# matrixkeypad.net
KiCad netlist of a schematic drawn in Altium Designer
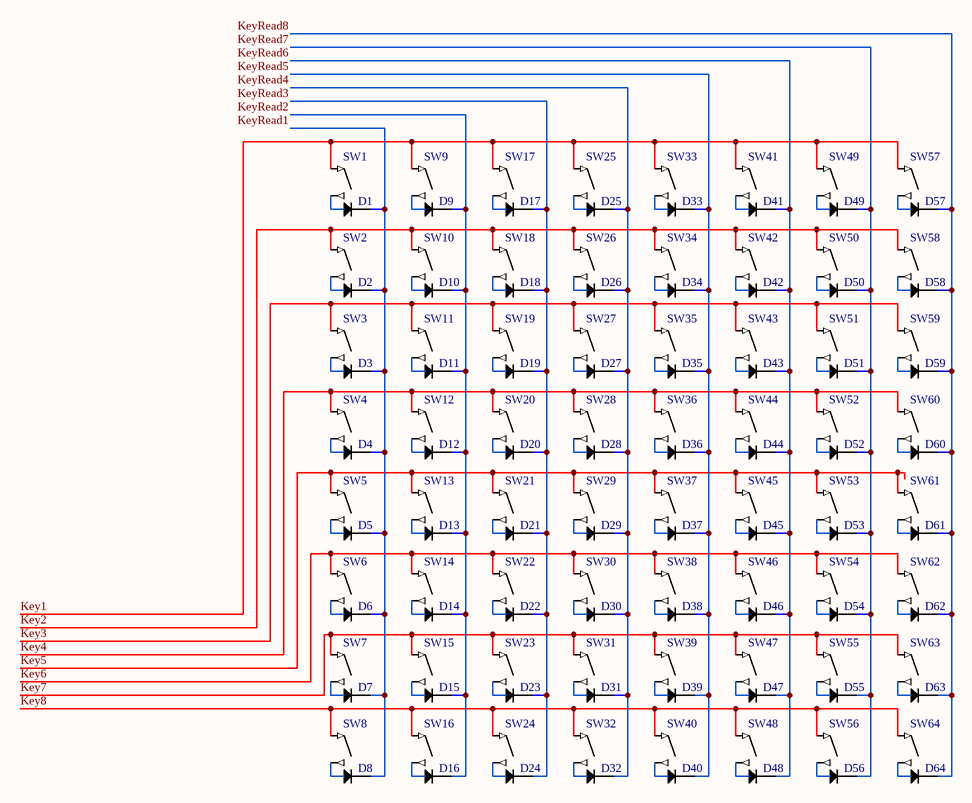
[diagram p0: matrixkeypad.SchDoc]

(export (version "E")
  (design (tool "Eeschema 10.0.6"))
  (components
    (comp (ref "D1") (value "1N4148") (footprint "SOD123") (libsource (lib "Project 64") (part "1N4148")))
    (comp (ref "D2") (value "1N4148") (footprint "SOD123") (libsource (lib "Project 64") (part "1N4148")))
    (comp (ref "D3") (value "1N4148") (footprint "SOD123") (libsource (lib "Project 64") (part "1N4148")))
    (comp (ref "D4") (value "1N4148") (footprint "SOD123") (libsource (lib "Project 64") (part "1N4148")))
    (comp (ref "D5") (value "1N4148") (footprint "SOD123") (libsource (lib "Project 64") (part "1N4148")))
    (comp (ref "D6") (value "1N4148") (footprint "SOD123") (libsource (lib "Project 64") (part "1N4148")))
    (comp (ref "D7") (value "1N4148") (footprint "SOD123") (libsource (lib "Project 64") (part "1N4148")))
    (comp (ref "D8") (value "1N4148") (footprint "SOD123") (libsource (lib "Project 64") (part "1N4148")))
    (comp (ref "D9") (value "1N4148") (footprint "SOD123") (libsource (lib "Project 64") (part "1N4148")))
    (comp (ref "D10") (value "1N4148") (footprint "SOD123") (libsource (lib "Project 64") (part "1N4148")))
    (comp (ref "D11") (value "1N4148") (footprint "SOD123") (libsource (lib "Project 64") (part "1N4148")))
    (comp (ref "D12") (value "1N4148") (footprint "SOD123") (libsource (lib "Project 64") (part "1N4148")))
    (comp (ref "D13") (value "1N4148") (footprint "SOD123") (libsource (lib "Project 64") (part "1N4148")))
    (comp (ref "D14") (value "1N4148") (footprint "SOD123") (libsource (lib "Project 64") (part "1N4148")))
    (comp (ref "D15") (value "1N4148") (footprint "SOD123") (libsource (lib "Project 64") (part "1N4148")))
    (comp (ref "D16") (value "1N4148") (footprint "SOD123") (libsource (lib "Project 64") (part "1N4148")))
    (comp (ref "D17") (value "1N4148") (footprint "SOD123") (libsource (lib "Project 64") (part "1N4148")))
    (comp (ref "D18") (value "1N4148") (footprint "SOD123") (libsource (lib "Project 64") (part "1N4148")))
    (comp (ref "D19") (value "1N4148") (footprint "SOD123") (libsource (lib "Project 64") (part "1N4148")))
    (comp (ref "D20") (value "1N4148") (footprint "SOD123") (libsource (lib "Project 64") (part "1N4148")))
    (comp (ref "D21") (value "1N4148") (footprint "SOD123") (libsource (lib "Project 64") (part "1N4148")))
    (comp (ref "D22") (value "1N4148") (footprint "SOD123") (libsource (lib "Project 64") (part "1N4148")))
    (comp (ref "D23") (value "1N4148") (footprint "SOD123") (libsource (lib "Project 64") (part "1N4148")))
    (comp (ref "D24") (value "1N4148") (footprint "SOD123") (libsource (lib "Project 64") (part "1N4148")))
    (comp (ref "D25") (value "1N4148") (footprint "SOD123") (libsource (lib "Project 64") (part "1N4148")))
    (comp (ref "D26") (value "1N4148") (footprint "SOD123") (libsource (lib "Project 64") (part "1N4148")))
    (comp (ref "D27") (value "1N4148") (footprint "SOD123") (libsource (lib "Project 64") (part "1N4148")))
    (comp (ref "D28") (value "1N4148") (footprint "SOD123") (libsource (lib "Project 64") (part "1N4148")))
    (comp (ref "D29") (value "1N4148") (footprint "SOD123") (libsource (lib "Project 64") (part "1N4148")))
    (comp (ref "D30") (value "1N4148") (footprint "SOD123") (libsource (lib "Project 64") (part "1N4148")))
    (comp (ref "D31") (value "1N4148") (footprint "SOD123") (libsource (lib "Project 64") (part "1N4148")))
    (comp (ref "D32") (value "1N4148") (footprint "SOD123") (libsource (lib "Project 64") (part "1N4148")))
    (comp (ref "D33") (value "1N4148") (footprint "SOD123") (libsource (lib "Project 64") (part "1N4148")))
    (comp (ref "D34") (value "1N4148") (footprint "SOD123") (libsource (lib "Project 64") (part "1N4148")))
    (comp (ref "D35") (value "1N4148") (footprint "SOD123") (libsource (lib "Project 64") (part "1N4148")))
    (comp (ref "D36") (value "1N4148") (footprint "SOD123") (libsource (lib "Project 64") (part "1N4148")))
    (comp (ref "D37") (value "1N4148") (footprint "SOD123") (libsource (lib "Project 64") (part "1N4148")))
    (comp (ref "D38") (value "1N4148") (footprint "SOD123") (libsource (lib "Project 64") (part "1N4148")))
    (comp (ref "D39") (value "1N4148") (footprint "SOD123") (libsource (lib "Project 64") (part "1N4148")))
    (comp (ref "D40") (value "1N4148") (footprint "SOD123") (libsource (lib "Project 64") (part "1N4148")))
    (comp (ref "D41") (value "1N4148") (footprint "SOD123") (libsource (lib "Project 64") (part "1N4148")))
    (comp (ref "D42") (value "1N4148") (footprint "SOD123") (libsource (lib "Project 64") (part "1N4148")))
    (comp (ref "D43") (value "1N4148") (footprint "SOD123") (libsource (lib "Project 64") (part "1N4148")))
    (comp (ref "D44") (value "1N4148") (footprint "SOD123") (libsource (lib "Project 64") (part "1N4148")))
    (comp (ref "D45") (value "1N4148") (footprint "SOD123") (libsource (lib "Project 64") (part "1N4148")))
    (comp (ref "D46") (value "1N4148") (footprint "SOD123") (libsource (lib "Project 64") (part "1N4148")))
    (comp (ref "D47") (value "1N4148") (footprint "SOD123") (libsource (lib "Project 64") (part "1N4148")))
    (comp (ref "D48") (value "1N4148") (footprint "SOD123") (libsource (lib "Project 64") (part "1N4148")))
    (comp (ref "D49") (value "1N4148") (footprint "SOD123") (libsource (lib "Project 64") (part "1N4148")))
    (comp (ref "D50") (value "1N4148") (footprint "SOD123") (libsource (lib "Project 64") (part "1N4148")))
    (comp (ref "D51") (value "1N4148") (footprint "SOD123") (libsource (lib "Project 64") (part "1N4148")))
    (comp (ref "D52") (value "1N4148") (footprint "SOD123") (libsource (lib "Project 64") (part "1N4148")))
    (comp (ref "D53") (value "1N4148") (footprint "SOD123") (libsource (lib "Project 64") (part "1N4148")))
    (comp (ref "D54") (value "1N4148") (footprint "SOD123") (libsource (lib "Project 64") (part "1N4148")))
    (comp (ref "D55") (value "1N4148") (footprint "SOD123") (libsource (lib "Project 64") (part "1N4148")))
    (comp (ref "D56") (value "1N4148") (footprint "SOD123") (libsource (lib "Project 64") (part "1N4148")))
    (comp (ref "D57") (value "1N4148") (footprint "SOD123") (libsource (lib "Project 64") (part "1N4148")))
    (comp (ref "D58") (value "1N4148") (footprint "SOD123") (libsource (lib "Project 64") (part "1N4148")))
    (comp (ref "D59") (value "1N4148") (footprint "SOD123") (libsource (lib "Project 64") (part "1N4148")))
    (comp (ref "D60") (value "1N4148") (footprint "SOD123") (libsource (lib "Project 64") (part "1N4148")))
    (comp (ref "D61") (value "1N4148") (footprint "SOD123") (libsource (lib "Project 64") (part "1N4148")))
    (comp (ref "D62") (value "1N4148") (footprint "SOD123") (libsource (lib "Project 64") (part "1N4148")))
    (comp (ref "D63") (value "1N4148") (footprint "SOD123") (libsource (lib "Project 64") (part "1N4148")))
    (comp (ref "D64") (value "1N4148") (footprint "SOD123") (libsource (lib "Project 64") (part "1N4148")))
    (comp (ref "SW1") (value "~") (footprint "PAD") (libsource (lib "Project 64") (part "SW")))
    (comp (ref "SW2") (value "~") (footprint "PAD") (libsource (lib "Project 64") (part "SW")))
    (comp (ref "SW3") (value "~") (footprint "PAD") (libsource (lib "Project 64") (part "SW")))
    (comp (ref "SW4") (value "~") (footprint "PAD") (libsource (lib "Project 64") (part "SW")))
    (comp (ref "SW5") (value "~") (footprint "PAD") (libsource (lib "Project 64") (part "SW")))
    (comp (ref "SW6") (value "~") (footprint "PAD") (libsource (lib "Project 64") (part "SW")))
    (comp (ref "SW7") (value "~") (footprint "PAD") (libsource (lib "Project 64") (part "SW")))
    (comp (ref "SW8") (value "~") (footprint "PAD") (libsource (lib "Project 64") (part "SW")))
    (comp (ref "SW9") (value "~") (footprint "PAD") (libsource (lib "Project 64") (part "SW")))
    (comp (ref "SW10") (value "~") (footprint "PAD") (libsource (lib "Project 64") (part "SW")))
    (comp (ref "SW11") (value "~") (footprint "PAD") (libsource (lib "Project 64") (part "SW")))
    (comp (ref "SW12") (value "~") (footprint "PAD") (libsource (lib "Project 64") (part "SW")))
    (comp (ref "SW13") (value "~") (footprint "PAD") (libsource (lib "Project 64") (part "SW")))
    (comp (ref "SW14") (value "~") (footprint "PAD") (libsource (lib "Project 64") (part "SW")))
    (comp (ref "SW15") (value "~") (footprint "PAD") (libsource (lib "Project 64") (part "SW")))
    (comp (ref "SW16") (value "~") (footprint "PAD") (libsource (lib "Project 64") (part "SW")))
    (comp (ref "SW17") (value "~") (footprint "PAD") (libsource (lib "Project 64") (part "SW")))
    (comp (ref "SW18") (value "~") (footprint "PAD") (libsource (lib "Project 64") (part "SW")))
    (comp (ref "SW19") (value "~") (footprint "PAD") (libsource (lib "Project 64") (part "SW")))
    (comp (ref "SW20") (value "~") (footprint "PAD") (libsource (lib "Project 64") (part "SW")))
    (comp (ref "SW21") (value "~") (footprint "PAD") (libsource (lib "Project 64") (part "SW")))
    (comp (ref "SW22") (value "~") (footprint "PAD") (libsource (lib "Project 64") (part "SW")))
    (comp (ref "SW23") (value "~") (footprint "PAD") (libsource (lib "Project 64") (part "SW")))
    (comp (ref "SW24") (value "~") (footprint "PAD") (libsource (lib "Project 64") (part "SW")))
    (comp (ref "SW25") (value "~") (footprint "PAD") (libsource (lib "Project 64") (part "SW")))
    (comp (ref "SW26") (value "~") (footprint "PAD") (libsource (lib "Project 64") (part "SW")))
    (comp (ref "SW27") (value "~") (footprint "PAD") (libsource (lib "Project 64") (part "SW")))
    (comp (ref "SW28") (value "~") (footprint "PAD") (libsource (lib "Project 64") (part "SW")))
    (comp (ref "SW29") (value "~") (footprint "PAD") (libsource (lib "Project 64") (part "SW")))
    (comp (ref "SW30") (value "~") (footprint "PAD") (libsource (lib "Project 64") (part "SW")))
    (comp (ref "SW31") (value "~") (footprint "PAD") (libsource (lib "Project 64") (part "SW")))
    (comp (ref "SW32") (value "~") (footprint "PAD") (libsource (lib "Project 64") (part "SW")))
    (comp (ref "SW33") (value "~") (footprint "PAD") (libsource (lib "Project 64") (part "SW")))
    (comp (ref "SW34") (value "~") (footprint "PAD") (libsource (lib "Project 64") (part "SW")))
    (comp (ref "SW35") (value "~") (footprint "PAD") (libsource (lib "Project 64") (part "SW")))
    (comp (ref "SW36") (value "~") (footprint "PAD") (libsource (lib "Project 64") (part "SW")))
    (comp (ref "SW37") (value "~") (footprint "PAD") (libsource (lib "Project 64") (part "SW")))
    (comp (ref "SW38") (value "~") (footprint "PAD") (libsource (lib "Project 64") (part "SW")))
    (comp (ref "SW39") (value "~") (footprint "PAD") (libsource (lib "Project 64") (part "SW")))
    (comp (ref "SW40") (value "~") (footprint "PAD") (libsource (lib "Project 64") (part "SW")))
    (comp (ref "SW41") (value "~") (footprint "PAD") (libsource (lib "Project 64") (part "SW")))
    (comp (ref "SW42") (value "~") (footprint "PAD") (libsource (lib "Project 64") (part "SW")))
    (comp (ref "SW43") (value "~") (footprint "PAD") (libsource (lib "Project 64") (part "SW")))
    (comp (ref "SW44") (value "~") (footprint "PAD") (libsource (lib "Project 64") (part "SW")))
    (comp (ref "SW45") (value "~") (footprint "PAD") (libsource (lib "Project 64") (part "SW")))
    (comp (ref "SW46") (value "~") (footprint "PAD") (libsource (lib "Project 64") (part "SW")))
    (comp (ref "SW47") (value "~") (footprint "PAD") (libsource (lib "Project 64") (part "SW")))
    (comp (ref "SW48") (value "~") (footprint "PAD") (libsource (lib "Project 64") (part "SW")))
    (comp (ref "SW49") (value "~") (footprint "PAD") (libsource (lib "Project 64") (part "SW")))
    (comp (ref "SW50") (value "~") (footprint "PAD") (libsource (lib "Project 64") (part "SW")))
    (comp (ref "SW51") (value "~") (footprint "PAD") (libsource (lib "Project 64") (part "SW")))
    (comp (ref "SW52") (value "~") (footprint "PAD") (libsource (lib "Project 64") (part "SW")))
    (comp (ref "SW53") (value "~") (footprint "PAD") (libsource (lib "Project 64") (part "SW")))
    (comp (ref "SW54") (value "~") (footprint "PAD") (libsource (lib "Project 64") (part "SW")))
    (comp (ref "SW55") (value "~") (footprint "PAD") (libsource (lib "Project 64") (part "SW")))
    (comp (ref "SW56") (value "~") (footprint "PAD") (libsource (lib "Project 64") (part "SW")))
    (comp (ref "SW57") (value "~") (footprint "PAD") (libsource (lib "Project 64") (part "SW")))
    (comp (ref "SW58") (value "~") (footprint "PAD") (libsource (lib "Project 64") (part "SW")))
    (comp (ref "SW59") (value "~") (footprint "PAD") (libsource (lib "Project 64") (part "SW")))
    (comp (ref "SW60") (value "~") (footprint "PAD") (libsource (lib "Project 64") (part "SW")))
    (comp (ref "SW61") (value "~") (footprint "PAD") (libsource (lib "Project 64") (part "SW")))
    (comp (ref "SW62") (value "~") (footprint "PAD") (libsource (lib "Project 64") (part "SW")))
    (comp (ref "SW63") (value "~") (footprint "PAD") (libsource (lib "Project 64") (part "SW")))
    (comp (ref "SW64") (value "~") (footprint "PAD") (libsource (lib "Project 64") (part "SW")))
  )
  (nets
    (net (code "1") (name "/Key1") (class "Default")
      (node (ref "SW1") (pin "1") (pinfunction "1_1") (pintype "input"))
      (node (ref "SW17") (pin "1") (pinfunction "1_1") (pintype "input"))
      (node (ref "SW25") (pin "1") (pinfunction "1_1") (pintype "input"))
      (node (ref "SW33") (pin "1") (pinfunction "1_1") (pintype "input"))
      (node (ref "SW41") (pin "1") (pinfunction "1_1") (pintype "input"))
      (node (ref "SW49") (pin "1") (pinfunction "1_1") (pintype "input"))
      (node (ref "SW57") (pin "1") (pinfunction "1_1") (pintype "input"))
      (node (ref "SW9") (pin "1") (pinfunction "1_1") (pintype "input"))
    )
    (net (code "2") (name "/Key2") (class "Default")
      (node (ref "SW10") (pin "1") (pinfunction "1_1") (pintype "input"))
      (node (ref "SW18") (pin "1") (pinfunction "1_1") (pintype "input"))
      (node (ref "SW2") (pin "1") (pinfunction "1_1") (pintype "input"))
      (node (ref "SW26") (pin "1") (pinfunction "1_1") (pintype "input"))
      (node (ref "SW34") (pin "1") (pinfunction "1_1") (pintype "input"))
      (node (ref "SW42") (pin "1") (pinfunction "1_1") (pintype "input"))
      (node (ref "SW50") (pin "1") (pinfunction "1_1") (pintype "input"))
      (node (ref "SW58") (pin "1") (pinfunction "1_1") (pintype "input"))
    )
    (net (code "3") (name "/Key3") (class "Default")
      (node (ref "SW11") (pin "1") (pinfunction "1_1") (pintype "input"))
      (node (ref "SW19") (pin "1") (pinfunction "1_1") (pintype "input"))
      (node (ref "SW27") (pin "1") (pinfunction "1_1") (pintype "input"))
      (node (ref "SW3") (pin "1") (pinfunction "1_1") (pintype "input"))
      (node (ref "SW35") (pin "1") (pinfunction "1_1") (pintype "input"))
      (node (ref "SW43") (pin "1") (pinfunction "1_1") (pintype "input"))
      (node (ref "SW51") (pin "1") (pinfunction "1_1") (pintype "input"))
      (node (ref "SW59") (pin "1") (pinfunction "1_1") (pintype "input"))
    )
    (net (code "4") (name "/Key4") (class "Default")
      (node (ref "SW12") (pin "1") (pinfunction "1_1") (pintype "input"))
      (node (ref "SW20") (pin "1") (pinfunction "1_1") (pintype "input"))
      (node (ref "SW28") (pin "1") (pinfunction "1_1") (pintype "input"))
      (node (ref "SW36") (pin "1") (pinfunction "1_1") (pintype "input"))
      (node (ref "SW4") (pin "1") (pinfunction "1_1") (pintype "input"))
      (node (ref "SW44") (pin "1") (pinfunction "1_1") (pintype "input"))
      (node (ref "SW52") (pin "1") (pinfunction "1_1") (pintype "input"))
      (node (ref "SW60") (pin "1") (pinfunction "1_1") (pintype "input"))
    )
    (net (code "5") (name "/Key5") (class "Default")
      (node (ref "SW13") (pin "1") (pinfunction "1_1") (pintype "input"))
      (node (ref "SW21") (pin "1") (pinfunction "1_1") (pintype "input"))
      (node (ref "SW29") (pin "1") (pinfunction "1_1") (pintype "input"))
      (node (ref "SW37") (pin "1") (pinfunction "1_1") (pintype "input"))
      (node (ref "SW45") (pin "1") (pinfunction "1_1") (pintype "input"))
      (node (ref "SW5") (pin "1") (pinfunction "1_1") (pintype "input"))
      (node (ref "SW53") (pin "1") (pinfunction "1_1") (pintype "input"))
      (node (ref "SW61") (pin "1") (pinfunction "1_1") (pintype "input"))
    )
    (net (code "6") (name "/Key6") (class "Default")
      (node (ref "SW14") (pin "1") (pinfunction "1_1") (pintype "input"))
      (node (ref "SW22") (pin "1") (pinfunction "1_1") (pintype "input"))
      (node (ref "SW30") (pin "1") (pinfunction "1_1") (pintype "input"))
      (node (ref "SW38") (pin "1") (pinfunction "1_1") (pintype "input"))
      (node (ref "SW46") (pin "1") (pinfunction "1_1") (pintype "input"))
      (node (ref "SW54") (pin "1") (pinfunction "1_1") (pintype "input"))
      (node (ref "SW6") (pin "1") (pinfunction "1_1") (pintype "input"))
      (node (ref "SW62") (pin "1") (pinfunction "1_1") (pintype "input"))
    )
    (net (code "7") (name "/Key7") (class "Default")
      (node (ref "SW15") (pin "1") (pinfunction "1_1") (pintype "input"))
      (node (ref "SW23") (pin "1") (pinfunction "1_1") (pintype "input"))
      (node (ref "SW31") (pin "1") (pinfunction "1_1") (pintype "input"))
      (node (ref "SW39") (pin "1") (pinfunction "1_1") (pintype "input"))
      (node (ref "SW47") (pin "1") (pinfunction "1_1") (pintype "input"))
      (node (ref "SW55") (pin "1") (pinfunction "1_1") (pintype "input"))
      (node (ref "SW63") (pin "1") (pinfunction "1_1") (pintype "input"))
      (node (ref "SW7") (pin "1") (pinfunction "1_1") (pintype "input"))
    )
    (net (code "8") (name "/Key8") (class "Default")
      (node (ref "SW16") (pin "1") (pinfunction "1_1") (pintype "input"))
      (node (ref "SW24") (pin "1") (pinfunction "1_1") (pintype "input"))
      (node (ref "SW32") (pin "1") (pinfunction "1_1") (pintype "input"))
      (node (ref "SW40") (pin "1") (pinfunction "1_1") (pintype "input"))
      (node (ref "SW48") (pin "1") (pinfunction "1_1") (pintype "input"))
      (node (ref "SW56") (pin "1") (pinfunction "1_1") (pintype "input"))
      (node (ref "SW64") (pin "1") (pinfunction "1_1") (pintype "input"))
      (node (ref "SW8") (pin "1") (pinfunction "1_1") (pintype "input"))
    )
    (net (code "9") (name "/KeyRead1") (class "Default")
      (node (ref "D1") (pin "2") (pinfunction "2_2") (pintype "passive"))
      (node (ref "D2") (pin "2") (pinfunction "2_2") (pintype "passive"))
      (node (ref "D3") (pin "2") (pinfunction "2_2") (pintype "passive"))
      (node (ref "D4") (pin "2") (pinfunction "2_2") (pintype "passive"))
      (node (ref "D5") (pin "2") (pinfunction "2_2") (pintype "passive"))
      (node (ref "D6") (pin "2") (pinfunction "2_2") (pintype "passive"))
      (node (ref "D7") (pin "2") (pinfunction "2_2") (pintype "passive"))
      (node (ref "D8") (pin "2") (pinfunction "2_2") (pintype "passive"))
    )
    (net (code "10") (name "/KeyRead2") (class "Default")
      (node (ref "D10") (pin "2") (pinfunction "2_2") (pintype "passive"))
      (node (ref "D11") (pin "2") (pinfunction "2_2") (pintype "passive"))
      (node (ref "D12") (pin "2") (pinfunction "2_2") (pintype "passive"))
      (node (ref "D13") (pin "2") (pinfunction "2_2") (pintype "passive"))
      (node (ref "D14") (pin "2") (pinfunction "2_2") (pintype "passive"))
      (node (ref "D15") (pin "2") (pinfunction "2_2") (pintype "passive"))
      (node (ref "D16") (pin "2") (pinfunction "2_2") (pintype "passive"))
      (node (ref "D9") (pin "2") (pinfunction "2_2") (pintype "passive"))
    )
    (net (code "11") (name "/KeyRead3") (class "Default")
      (node (ref "D17") (pin "2") (pinfunction "2_2") (pintype "passive"))
      (node (ref "D18") (pin "2") (pinfunction "2_2") (pintype "passive"))
      (node (ref "D19") (pin "2") (pinfunction "2_2") (pintype "passive"))
      (node (ref "D20") (pin "2") (pinfunction "2_2") (pintype "passive"))
      (node (ref "D21") (pin "2") (pinfunction "2_2") (pintype "passive"))
      (node (ref "D22") (pin "2") (pinfunction "2_2") (pintype "passive"))
      (node (ref "D23") (pin "2") (pinfunction "2_2") (pintype "passive"))
      (node (ref "D24") (pin "2") (pinfunction "2_2") (pintype "passive"))
    )
    (net (code "12") (name "/KeyRead4") (class "Default")
      (node (ref "D25") (pin "2") (pinfunction "2_2") (pintype "passive"))
      (node (ref "D26") (pin "2") (pinfunction "2_2") (pintype "passive"))
      (node (ref "D27") (pin "2") (pinfunction "2_2") (pintype "passive"))
      (node (ref "D28") (pin "2") (pinfunction "2_2") (pintype "passive"))
      (node (ref "D29") (pin "2") (pinfunction "2_2") (pintype "passive"))
      (node (ref "D30") (pin "2") (pinfunction "2_2") (pintype "passive"))
      (node (ref "D31") (pin "2") (pinfunction "2_2") (pintype "passive"))
      (node (ref "D32") (pin "2") (pinfunction "2_2") (pintype "passive"))
    )
    (net (code "13") (name "/KeyRead5") (class "Default")
      (node (ref "D33") (pin "2") (pinfunction "2_2") (pintype "passive"))
      (node (ref "D34") (pin "2") (pinfunction "2_2") (pintype "passive"))
      (node (ref "D35") (pin "2") (pinfunction "2_2") (pintype "passive"))
      (node (ref "D36") (pin "2") (pinfunction "2_2") (pintype "passive"))
      (node (ref "D37") (pin "2") (pinfunction "2_2") (pintype "passive"))
      (node (ref "D38") (pin "2") (pinfunction "2_2") (pintype "passive"))
      (node (ref "D39") (pin "2") (pinfunction "2_2") (pintype "passive"))
      (node (ref "D40") (pin "2") (pinfunction "2_2") (pintype "passive"))
    )
    (net (code "14") (name "/KeyRead6") (class "Default")
      (node (ref "D41") (pin "2") (pinfunction "2_2") (pintype "passive"))
      (node (ref "D42") (pin "2") (pinfunction "2_2") (pintype "passive"))
      (node (ref "D43") (pin "2") (pinfunction "2_2") (pintype "passive"))
      (node (ref "D44") (pin "2") (pinfunction "2_2") (pintype "passive"))
      (node (ref "D45") (pin "2") (pinfunction "2_2") (pintype "passive"))
      (node (ref "D46") (pin "2") (pinfunction "2_2") (pintype "passive"))
      (node (ref "D47") (pin "2") (pinfunction "2_2") (pintype "passive"))
      (node (ref "D48") (pin "2") (pinfunction "2_2") (pintype "passive"))
    )
    (net (code "15") (name "/KeyRead7") (class "Default")
      (node (ref "D49") (pin "2") (pinfunction "2_2") (pintype "passive"))
      (node (ref "D50") (pin "2") (pinfunction "2_2") (pintype "passive"))
      (node (ref "D51") (pin "2") (pinfunction "2_2") (pintype "passive"))
      (node (ref "D52") (pin "2") (pinfunction "2_2") (pintype "passive"))
      (node (ref "D53") (pin "2") (pinfunction "2_2") (pintype "passive"))
      (node (ref "D54") (pin "2") (pinfunction "2_2") (pintype "passive"))
      (node (ref "D55") (pin "2") (pinfunction "2_2") (pintype "passive"))
      (node (ref "D56") (pin "2") (pinfunction "2_2") (pintype "passive"))
    )
    (net (code "16") (name "/KeyRead8") (class "Default")
      (node (ref "D57") (pin "2") (pinfunction "2_2") (pintype "passive"))
      (node (ref "D58") (pin "2") (pinfunction "2_2") (pintype "passive"))
      (node (ref "D59") (pin "2") (pinfunction "2_2") (pintype "passive"))
      (node (ref "D60") (pin "2") (pinfunction "2_2") (pintype "passive"))
      (node (ref "D61") (pin "2") (pinfunction "2_2") (pintype "passive"))
      (node (ref "D62") (pin "2") (pinfunction "2_2") (pintype "passive"))
      (node (ref "D63") (pin "2") (pinfunction "2_2") (pintype "passive"))
      (node (ref "D64") (pin "2") (pinfunction "2_2") (pintype "passive"))
    )
    (net (code "17") (name "Net-(SW1-Out)") (class "Default")
      (node (ref "D1") (pin "1") (pinfunction "1_1") (pintype "passive"))
      (node (ref "SW1") (pin "2") (pinfunction "Out_2") (pintype "output"))
    )
    (net (code "18") (name "Net-(SW2-Out)") (class "Default")
      (node (ref "D2") (pin "1") (pinfunction "1_1") (pintype "passive"))
      (node (ref "SW2") (pin "2") (pinfunction "Out_2") (pintype "output"))
    )
    (net (code "19") (name "Net-(SW3-Out)") (class "Default")
      (node (ref "D3") (pin "1") (pinfunction "1_1") (pintype "passive"))
      (node (ref "SW3") (pin "2") (pinfunction "Out_2") (pintype "output"))
    )
    (net (code "20") (name "Net-(SW4-Out)") (class "Default")
      (node (ref "D4") (pin "1") (pinfunction "1_1") (pintype "passive"))
      (node (ref "SW4") (pin "2") (pinfunction "Out_2") (pintype "output"))
    )
    (net (code "21") (name "Net-(SW5-Out)") (class "Default")
      (node (ref "D5") (pin "1") (pinfunction "1_1") (pintype "passive"))
      (node (ref "SW5") (pin "2") (pinfunction "Out_2") (pintype "output"))
    )
    (net (code "22") (name "Net-(SW6-Out)") (class "Default")
      (node (ref "D6") (pin "1") (pinfunction "1_1") (pintype "passive"))
      (node (ref "SW6") (pin "2") (pinfunction "Out_2") (pintype "output"))
    )
    (net (code "23") (name "Net-(SW7-Out)") (class "Default")
      (node (ref "D7") (pin "1") (pinfunction "1_1") (pintype "passive"))
      (node (ref "SW7") (pin "2") (pinfunction "Out_2") (pintype "output"))
    )
    (net (code "24") (name "Net-(SW8-Out)") (class "Default")
      (node (ref "D8") (pin "1") (pinfunction "1_1") (pintype "passive"))
      (node (ref "SW8") (pin "2") (pinfunction "Out_2") (pintype "output"))
    )
    (net (code "25") (name "Net-(SW9-Out)") (class "Default")
      (node (ref "D9") (pin "1") (pinfunction "1_1") (pintype "passive"))
      (node (ref "SW9") (pin "2") (pinfunction "Out_2") (pintype "output"))
    )
    (net (code "26") (name "Net-(SW10-Out)") (class "Default")
      (node (ref "D10") (pin "1") (pinfunction "1_1") (pintype "passive"))
      (node (ref "SW10") (pin "2") (pinfunction "Out_2") (pintype "output"))
    )
    (net (code "27") (name "Net-(SW11-Out)") (class "Default")
      (node (ref "D11") (pin "1") (pinfunction "1_1") (pintype "passive"))
      (node (ref "SW11") (pin "2") (pinfunction "Out_2") (pintype "output"))
    )
    (net (code "28") (name "Net-(SW12-Out)") (class "Default")
      (node (ref "D12") (pin "1") (pinfunction "1_1") (pintype "passive"))
      (node (ref "SW12") (pin "2") (pinfunction "Out_2") (pintype "output"))
    )
    (net (code "29") (name "Net-(SW13-Out)") (class "Default")
      (node (ref "D13") (pin "1") (pinfunction "1_1") (pintype "passive"))
      (node (ref "SW13") (pin "2") (pinfunction "Out_2") (pintype "output"))
    )
    (net (code "30") (name "Net-(SW14-Out)") (class "Default")
      (node (ref "D14") (pin "1") (pinfunction "1_1") (pintype "passive"))
      (node (ref "SW14") (pin "2") (pinfunction "Out_2") (pintype "output"))
    )
    (net (code "31") (name "Net-(SW15-Out)") (class "Default")
      (node (ref "D15") (pin "1") (pinfunction "1_1") (pintype "passive"))
      (node (ref "SW15") (pin "2") (pinfunction "Out_2") (pintype "output"))
    )
    (net (code "32") (name "Net-(SW16-Out)") (class "Default")
      (node (ref "D16") (pin "1") (pinfunction "1_1") (pintype "passive"))
      (node (ref "SW16") (pin "2") (pinfunction "Out_2") (pintype "output"))
    )
    (net (code "33") (name "Net-(SW17-Out)") (class "Default")
      (node (ref "D17") (pin "1") (pinfunction "1_1") (pintype "passive"))
      (node (ref "SW17") (pin "2") (pinfunction "Out_2") (pintype "output"))
    )
    (net (code "34") (name "Net-(SW18-Out)") (class "Default")
      (node (ref "D18") (pin "1") (pinfunction "1_1") (pintype "passive"))
      (node (ref "SW18") (pin "2") (pinfunction "Out_2") (pintype "output"))
    )
    (net (code "35") (name "Net-(SW19-Out)") (class "Default")
      (node (ref "D19") (pin "1") (pinfunction "1_1") (pintype "passive"))
      (node (ref "SW19") (pin "2") (pinfunction "Out_2") (pintype "output"))
    )
    (net (code "36") (name "Net-(SW20-Out)") (class "Default")
      (node (ref "D20") (pin "1") (pinfunction "1_1") (pintype "passive"))
      (node (ref "SW20") (pin "2") (pinfunction "Out_2") (pintype "output"))
    )
    (net (code "37") (name "Net-(SW21-Out)") (class "Default")
      (node (ref "D21") (pin "1") (pinfunction "1_1") (pintype "passive"))
      (node (ref "SW21") (pin "2") (pinfunction "Out_2") (pintype "output"))
    )
    (net (code "38") (name "Net-(SW22-Out)") (class "Default")
      (node (ref "D22") (pin "1") (pinfunction "1_1") (pintype "passive"))
      (node (ref "SW22") (pin "2") (pinfunction "Out_2") (pintype "output"))
    )
    (net (code "39") (name "Net-(SW23-Out)") (class "Default")
      (node (ref "D23") (pin "1") (pinfunction "1_1") (pintype "passive"))
      (node (ref "SW23") (pin "2") (pinfunction "Out_2") (pintype "output"))
    )
    (net (code "40") (name "Net-(SW24-Out)") (class "Default")
      (node (ref "D24") (pin "1") (pinfunction "1_1") (pintype "passive"))
      (node (ref "SW24") (pin "2") (pinfunction "Out_2") (pintype "output"))
    )
    (net (code "41") (name "Net-(SW25-Out)") (class "Default")
      (node (ref "D25") (pin "1") (pinfunction "1_1") (pintype "passive"))
      (node (ref "SW25") (pin "2") (pinfunction "Out_2") (pintype "output"))
    )
    (net (code "42") (name "Net-(SW26-Out)") (class "Default")
      (node (ref "D26") (pin "1") (pinfunction "1_1") (pintype "passive"))
      (node (ref "SW26") (pin "2") (pinfunction "Out_2") (pintype "output"))
    )
    (net (code "43") (name "Net-(SW27-Out)") (class "Default")
      (node (ref "D27") (pin "1") (pinfunction "1_1") (pintype "passive"))
      (node (ref "SW27") (pin "2") (pinfunction "Out_2") (pintype "output"))
    )
    (net (code "44") (name "Net-(SW28-Out)") (class "Default")
      (node (ref "D28") (pin "1") (pinfunction "1_1") (pintype "passive"))
      (node (ref "SW28") (pin "2") (pinfunction "Out_2") (pintype "output"))
    )
    (net (code "45") (name "Net-(SW29-Out)") (class "Default")
      (node (ref "D29") (pin "1") (pinfunction "1_1") (pintype "passive"))
      (node (ref "SW29") (pin "2") (pinfunction "Out_2") (pintype "output"))
    )
    (net (code "46") (name "Net-(SW30-Out)") (class "Default")
      (node (ref "D30") (pin "1") (pinfunction "1_1") (pintype "passive"))
      (node (ref "SW30") (pin "2") (pinfunction "Out_2") (pintype "output"))
    )
    (net (code "47") (name "Net-(SW31-Out)") (class "Default")
      (node (ref "D31") (pin "1") (pinfunction "1_1") (pintype "passive"))
      (node (ref "SW31") (pin "2") (pinfunction "Out_2") (pintype "output"))
    )
    (net (code "48") (name "Net-(SW32-Out)") (class "Default")
      (node (ref "D32") (pin "1") (pinfunction "1_1") (pintype "passive"))
      (node (ref "SW32") (pin "2") (pinfunction "Out_2") (pintype "output"))
    )
    (net (code "49") (name "Net-(SW33-Out)") (class "Default")
      (node (ref "D33") (pin "1") (pinfunction "1_1") (pintype "passive"))
      (node (ref "SW33") (pin "2") (pinfunction "Out_2") (pintype "output"))
    )
    (net (code "50") (name "Net-(SW34-Out)") (class "Default")
      (node (ref "D34") (pin "1") (pinfunction "1_1") (pintype "passive"))
      (node (ref "SW34") (pin "2") (pinfunction "Out_2") (pintype "output"))
    )
    (net (code "51") (name "Net-(SW35-Out)") (class "Default")
      (node (ref "D35") (pin "1") (pinfunction "1_1") (pintype "passive"))
      (node (ref "SW35") (pin "2") (pinfunction "Out_2") (pintype "output"))
    )
    (net (code "52") (name "Net-(SW36-Out)") (class "Default")
      (node (ref "D36") (pin "1") (pinfunction "1_1") (pintype "passive"))
      (node (ref "SW36") (pin "2") (pinfunction "Out_2") (pintype "output"))
    )
    (net (code "53") (name "Net-(SW37-Out)") (class "Default")
      (node (ref "D37") (pin "1") (pinfunction "1_1") (pintype "passive"))
      (node (ref "SW37") (pin "2") (pinfunction "Out_2") (pintype "output"))
    )
    (net (code "54") (name "Net-(SW38-Out)") (class "Default")
      (node (ref "D38") (pin "1") (pinfunction "1_1") (pintype "passive"))
      (node (ref "SW38") (pin "2") (pinfunction "Out_2") (pintype "output"))
    )
    (net (code "55") (name "Net-(SW39-Out)") (class "Default")
      (node (ref "D39") (pin "1") (pinfunction "1_1") (pintype "passive"))
      (node (ref "SW39") (pin "2") (pinfunction "Out_2") (pintype "output"))
    )
    (net (code "56") (name "Net-(SW40-Out)") (class "Default")
      (node (ref "D40") (pin "1") (pinfunction "1_1") (pintype "passive"))
      (node (ref "SW40") (pin "2") (pinfunction "Out_2") (pintype "output"))
    )
    (net (code "57") (name "Net-(SW41-Out)") (class "Default")
      (node (ref "D41") (pin "1") (pinfunction "1_1") (pintype "passive"))
      (node (ref "SW41") (pin "2") (pinfunction "Out_2") (pintype "output"))
    )
    (net (code "58") (name "Net-(SW42-Out)") (class "Default")
      (node (ref "D42") (pin "1") (pinfunction "1_1") (pintype "passive"))
      (node (ref "SW42") (pin "2") (pinfunction "Out_2") (pintype "output"))
    )
    (net (code "59") (name "Net-(SW43-Out)") (class "Default")
      (node (ref "D43") (pin "1") (pinfunction "1_1") (pintype "passive"))
      (node (ref "SW43") (pin "2") (pinfunction "Out_2") (pintype "output"))
    )
    (net (code "60") (name "Net-(SW44-Out)") (class "Default")
      (node (ref "D44") (pin "1") (pinfunction "1_1") (pintype "passive"))
      (node (ref "SW44") (pin "2") (pinfunction "Out_2") (pintype "output"))
    )
    (net (code "61") (name "Net-(SW45-Out)") (class "Default")
      (node (ref "D45") (pin "1") (pinfunction "1_1") (pintype "passive"))
      (node (ref "SW45") (pin "2") (pinfunction "Out_2") (pintype "output"))
    )
    (net (code "62") (name "Net-(SW46-Out)") (class "Default")
      (node (ref "D46") (pin "1") (pinfunction "1_1") (pintype "passive"))
      (node (ref "SW46") (pin "2") (pinfunction "Out_2") (pintype "output"))
    )
    (net (code "63") (name "Net-(SW47-Out)") (class "Default")
      (node (ref "D47") (pin "1") (pinfunction "1_1") (pintype "passive"))
      (node (ref "SW47") (pin "2") (pinfunction "Out_2") (pintype "output"))
    )
    (net (code "64") (name "Net-(SW48-Out)") (class "Default")
      (node (ref "D48") (pin "1") (pinfunction "1_1") (pintype "passive"))
      (node (ref "SW48") (pin "2") (pinfunction "Out_2") (pintype "output"))
    )
    (net (code "65") (name "Net-(SW49-Out)") (class "Default")
      (node (ref "D49") (pin "1") (pinfunction "1_1") (pintype "passive"))
      (node (ref "SW49") (pin "2") (pinfunction "Out_2") (pintype "output"))
    )
    (net (code "66") (name "Net-(SW50-Out)") (class "Default")
      (node (ref "D50") (pin "1") (pinfunction "1_1") (pintype "passive"))
      (node (ref "SW50") (pin "2") (pinfunction "Out_2") (pintype "output"))
    )
    (net (code "67") (name "Net-(SW51-Out)") (class "Default")
      (node (ref "D51") (pin "1") (pinfunction "1_1") (pintype "passive"))
      (node (ref "SW51") (pin "2") (pinfunction "Out_2") (pintype "output"))
    )
    (net (code "68") (name "Net-(SW52-Out)") (class "Default")
      (node (ref "D52") (pin "1") (pinfunction "1_1") (pintype "passive"))
      (node (ref "SW52") (pin "2") (pinfunction "Out_2") (pintype "output"))
    )
    (net (code "69") (name "Net-(SW53-Out)") (class "Default")
      (node (ref "D53") (pin "1") (pinfunction "1_1") (pintype "passive"))
      (node (ref "SW53") (pin "2") (pinfunction "Out_2") (pintype "output"))
    )
    (net (code "70") (name "Net-(SW54-Out)") (class "Default")
      (node (ref "D54") (pin "1") (pinfunction "1_1") (pintype "passive"))
      (node (ref "SW54") (pin "2") (pinfunction "Out_2") (pintype "output"))
    )
    (net (code "71") (name "Net-(SW55-Out)") (class "Default")
      (node (ref "D55") (pin "1") (pinfunction "1_1") (pintype "passive"))
      (node (ref "SW55") (pin "2") (pinfunction "Out_2") (pintype "output"))
    )
    (net (code "72") (name "Net-(SW56-Out)") (class "Default")
      (node (ref "D56") (pin "1") (pinfunction "1_1") (pintype "passive"))
      (node (ref "SW56") (pin "2") (pinfunction "Out_2") (pintype "output"))
    )
    (net (code "73") (name "Net-(SW57-Out)") (class "Default")
      (node (ref "D57") (pin "1") (pinfunction "1_1") (pintype "passive"))
      (node (ref "SW57") (pin "2") (pinfunction "Out_2") (pintype "output"))
    )
    (net (code "74") (name "Net-(SW58-Out)") (class "Default")
      (node (ref "D58") (pin "1") (pinfunction "1_1") (pintype "passive"))
      (node (ref "SW58") (pin "2") (pinfunction "Out_2") (pintype "output"))
    )
    (net (code "75") (name "Net-(SW59-Out)") (class "Default")
      (node (ref "D59") (pin "1") (pinfunction "1_1") (pintype "passive"))
      (node (ref "SW59") (pin "2") (pinfunction "Out_2") (pintype "output"))
    )
    (net (code "76") (name "Net-(SW60-Out)") (class "Default")
      (node (ref "D60") (pin "1") (pinfunction "1_1") (pintype "passive"))
      (node (ref "SW60") (pin "2") (pinfunction "Out_2") (pintype "output"))
    )
    (net (code "77") (name "Net-(SW61-Out)") (class "Default")
      (node (ref "D61") (pin "1") (pinfunction "1_1") (pintype "passive"))
      (node (ref "SW61") (pin "2") (pinfunction "Out_2") (pintype "output"))
    )
    (net (code "78") (name "Net-(SW62-Out)") (class "Default")
      (node (ref "D62") (pin "1") (pinfunction "1_1") (pintype "passive"))
      (node (ref "SW62") (pin "2") (pinfunction "Out_2") (pintype "output"))
    )
    (net (code "79") (name "Net-(SW63-Out)") (class "Default")
      (node (ref "D63") (pin "1") (pinfunction "1_1") (pintype "passive"))
      (node (ref "SW63") (pin "2") (pinfunction "Out_2") (pintype "output"))
    )
    (net (code "80") (name "Net-(SW64-Out)") (class "Default")
      (node (ref "D64") (pin "1") (pinfunction "1_1") (pintype "passive"))
      (node (ref "SW64") (pin "2") (pinfunction "Out_2") (pintype "output"))
    )
  )
)
